# Teensy-Maxuino-Slave-A4988-stepper_2x_sh.net
KiCad netlist of a schematic drawn in EAGLE
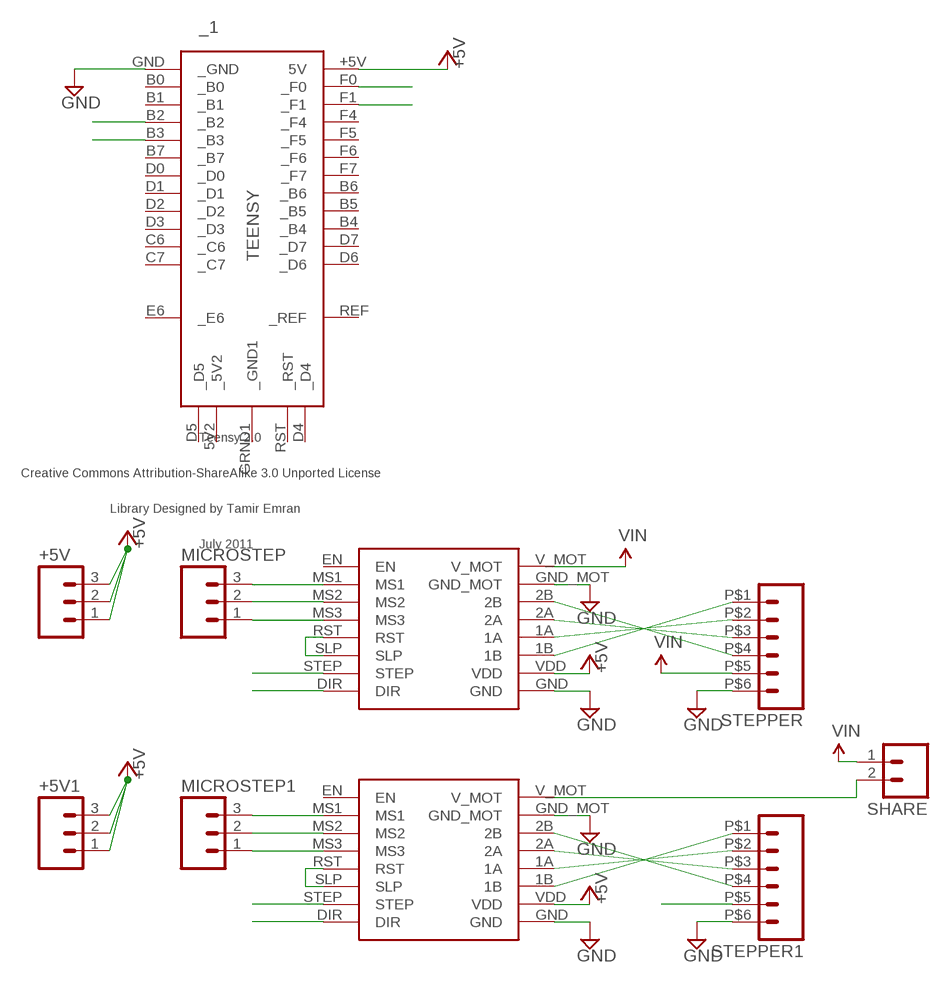
[diagram p0: schematic, sheet 1]

(export (version "E")
  (design (tool "Eeschema 10.0.6"))
  (components
    (comp (ref "+5V")
      (value "M03PTH")
      (footprint "eagle-import:1X03")
      (libsource (lib "eagle-import") (part "M03PTH"))
    )
    (comp (ref "+5V1")
      (value "M03PTH")
      (footprint "eagle-import:1X03")
      (libsource (lib "eagle-import") (part "M03PTH"))
    )
    (comp (ref "A4988_1")
      (value "POLOLU_A4988")
      (footprint "eagle-import:POLOLU_A4988")
      (libsource (lib "eagle-import") (part "POLOLU_A4988"))
    )
    (comp (ref "A4988_2")
      (value "POLOLU_A4988")
      (footprint "eagle-import:POLOLU_A4988")
      (libsource (lib "eagle-import") (part "POLOLU_A4988"))
    )
    (comp (ref "MICROSTEP")
      (value "M03PTH")
      (footprint "eagle-import:1X03")
      (libsource (lib "eagle-import") (part "M03PTH"))
    )
    (comp (ref "MICROSTEP1")
      (value "M03PTH")
      (footprint "eagle-import:1X03")
      (libsource (lib "eagle-import") (part "M03PTH"))
    )
    (comp (ref "SHARE")
      (value "M02PTH")
      (footprint "eagle-import:1X02")
      (libsource (lib "eagle-import") (part "M02PTH"))
    )
    (comp (ref "STEPPER")
      (value "M06")
      (footprint "eagle-import:SPRINGTERMINAL-2.54MM-6")
      (libsource (lib "eagle-import") (part "M06"))
    )
    (comp (ref "STEPPER1")
      (value "M06")
      (footprint "eagle-import:SPRINGTERMINAL-2.54MM-6")
      (libsource (lib "eagle-import") (part "M06"))
    )
    (comp (ref "_1")
      (value "TEENSY")
      (footprint "eagle-import:TEENSY")
      (libsource (lib "eagle-import") (part "TEENSY"))
    )
  )
  (nets
    (net (code "1") (name "+5V") (class "Default")
      (node (ref "+5V") (pin "1") (pinfunction "1_1") (pintype "passive"))
      (node (ref "+5V") (pin "2") (pinfunction "2_2") (pintype "passive"))
      (node (ref "+5V") (pin "3") (pinfunction "3_3") (pintype "passive"))
      (node (ref "+5V1") (pin "1") (pinfunction "1_1") (pintype "passive"))
      (node (ref "+5V1") (pin "2") (pinfunction "2_2") (pintype "passive"))
      (node (ref "+5V1") (pin "3") (pinfunction "3_3") (pintype "passive"))
      (node (ref "A4988_1") (pin "VDD") (pinfunction "VDD_VDD") (pintype "bidirectional"))
      (node (ref "A4988_2") (pin "VDD") (pinfunction "VDD_VDD") (pintype "bidirectional"))
      (node (ref "_1") (pin "+5V") (pinfunction "5V_+5V") (pintype "bidirectional"))
    )
    (net (code "2") (name "/DIR") (class "Default")
      (node (ref "A4988_1") (pin "DIR") (pinfunction "DIR_DIR") (pintype "bidirectional"))
      (node (ref "_1") (pin "F0") (pinfunction "_F0_F0") (pintype "bidirectional"))
    )
    (net (code "3") (name "/DIR1") (class "Default")
      (node (ref "A4988_2") (pin "DIR") (pinfunction "DIR_DIR") (pintype "bidirectional"))
      (node (ref "_1") (pin "B3") (pinfunction "_B3_B3") (pintype "bidirectional"))
    )
    (net (code "4") (name "/STEP") (class "Default")
      (node (ref "A4988_1") (pin "STEP") (pinfunction "STEP_STEP") (pintype "bidirectional"))
      (node (ref "_1") (pin "F1") (pinfunction "_F1_F1") (pintype "bidirectional"))
    )
    (net (code "5") (name "/STEP1") (class "Default")
      (node (ref "A4988_2") (pin "STEP") (pinfunction "STEP_STEP") (pintype "bidirectional"))
      (node (ref "_1") (pin "B2") (pinfunction "_B2_B2") (pintype "bidirectional"))
    )
    (net (code "6") (name "/VIN_2") (class "Default")
      (node (ref "A4988_2") (pin "V_MOT") (pinfunction "V_MOT_V_MOT") (pintype "bidirectional"))
      (node (ref "SHARE") (pin "2") (pinfunction "2_2") (pintype "passive"))
      (node (ref "STEPPER1") (pin "P$5") (pinfunction "5_P$5") (pintype "passive"))
    )
    (net (code "7") (name "GND") (class "Default")
      (node (ref "A4988_1") (pin "GND") (pinfunction "GND_GND") (pintype "bidirectional"))
      (node (ref "A4988_1") (pin "GND_MOT") (pinfunction "GND_MOT_GND_MOT") (pintype "bidirectional"))
      (node (ref "A4988_2") (pin "GND") (pinfunction "GND_GND") (pintype "bidirectional"))
      (node (ref "A4988_2") (pin "GND_MOT") (pinfunction "GND_MOT_GND_MOT") (pintype "bidirectional"))
      (node (ref "STEPPER") (pin "P$6") (pinfunction "6_P$6") (pintype "passive"))
      (node (ref "STEPPER1") (pin "P$6") (pinfunction "6_P$6") (pintype "passive"))
      (node (ref "_1") (pin "GND") (pinfunction "_GND_GND") (pintype "bidirectional"))
    )
    (net (code "8") (name "Net-(A4988_1-PadMS1)") (class "Default")
      (node (ref "A4988_1") (pin "MS1") (pinfunction "MS1_MS1") (pintype "bidirectional"))
      (node (ref "MICROSTEP") (pin "3") (pinfunction "3_3") (pintype "passive"))
    )
    (net (code "9") (name "Net-(A4988_1-PadMS2)") (class "Default")
      (node (ref "A4988_1") (pin "MS2") (pinfunction "MS2_MS2") (pintype "bidirectional"))
      (node (ref "MICROSTEP") (pin "2") (pinfunction "2_2") (pintype "passive"))
    )
    (net (code "10") (name "Net-(A4988_1-PadMS3)") (class "Default")
      (node (ref "A4988_1") (pin "MS3") (pinfunction "MS3_MS3") (pintype "bidirectional"))
      (node (ref "MICROSTEP") (pin "1") (pinfunction "1_1") (pintype "passive"))
    )
    (net (code "11") (name "Net-(A4988_1-PadRST)") (class "Default")
      (node (ref "A4988_1") (pin "RST") (pinfunction "RST_RST") (pintype "bidirectional"))
      (node (ref "A4988_1") (pin "SLP") (pinfunction "SLP_SLP") (pintype "bidirectional"))
    )
    (net (code "12") (name "Net-(A4988_2-PadMS1)") (class "Default")
      (node (ref "A4988_2") (pin "MS1") (pinfunction "MS1_MS1") (pintype "bidirectional"))
      (node (ref "MICROSTEP1") (pin "3") (pinfunction "3_3") (pintype "passive"))
    )
    (net (code "13") (name "Net-(A4988_2-PadMS2)") (class "Default")
      (node (ref "A4988_2") (pin "MS2") (pinfunction "MS2_MS2") (pintype "bidirectional"))
      (node (ref "MICROSTEP1") (pin "2") (pinfunction "2_2") (pintype "passive"))
    )
    (net (code "14") (name "Net-(A4988_2-PadMS3)") (class "Default")
      (node (ref "A4988_2") (pin "MS3") (pinfunction "MS3_MS3") (pintype "bidirectional"))
      (node (ref "MICROSTEP1") (pin "1") (pinfunction "1_1") (pintype "passive"))
    )
    (net (code "15") (name "Net-(A4988_2-PadRST)") (class "Default")
      (node (ref "A4988_2") (pin "RST") (pinfunction "RST_RST") (pintype "bidirectional"))
      (node (ref "A4988_2") (pin "SLP") (pinfunction "SLP_SLP") (pintype "bidirectional"))
    )
    (net (code "16") (name "Net-(STEPPER-1)") (class "Default")
      (node (ref "A4988_1") (pin "1B") (pinfunction "1B_1B") (pintype "bidirectional"))
      (node (ref "STEPPER") (pin "P$1") (pinfunction "1_P$1") (pintype "passive"))
    )
    (net (code "17") (name "Net-(STEPPER-2)") (class "Default")
      (node (ref "A4988_1") (pin "1A") (pinfunction "1A_1A") (pintype "bidirectional"))
      (node (ref "STEPPER") (pin "P$2") (pinfunction "2_P$2") (pintype "passive"))
    )
    (net (code "18") (name "Net-(STEPPER-3)") (class "Default")
      (node (ref "A4988_1") (pin "2A") (pinfunction "2A_2A") (pintype "bidirectional"))
      (node (ref "STEPPER") (pin "P$3") (pinfunction "3_P$3") (pintype "passive"))
    )
    (net (code "19") (name "Net-(STEPPER-4)") (class "Default")
      (node (ref "A4988_1") (pin "2B") (pinfunction "2B_2B") (pintype "bidirectional"))
      (node (ref "STEPPER") (pin "P$4") (pinfunction "4_P$4") (pintype "passive"))
    )
    (net (code "20") (name "Net-(STEPPER1-1)") (class "Default")
      (node (ref "A4988_2") (pin "1B") (pinfunction "1B_1B") (pintype "bidirectional"))
      (node (ref "STEPPER1") (pin "P$1") (pinfunction "1_P$1") (pintype "passive"))
    )
    (net (code "21") (name "Net-(STEPPER1-2)") (class "Default")
      (node (ref "A4988_2") (pin "1A") (pinfunction "1A_1A") (pintype "bidirectional"))
      (node (ref "STEPPER1") (pin "P$2") (pinfunction "2_P$2") (pintype "passive"))
    )
    (net (code "22") (name "Net-(STEPPER1-3)") (class "Default")
      (node (ref "A4988_2") (pin "2A") (pinfunction "2A_2A") (pintype "bidirectional"))
      (node (ref "STEPPER1") (pin "P$3") (pinfunction "3_P$3") (pintype "passive"))
    )
    (net (code "23") (name "Net-(STEPPER1-4)") (class "Default")
      (node (ref "A4988_2") (pin "2B") (pinfunction "2B_2B") (pintype "bidirectional"))
      (node (ref "STEPPER1") (pin "P$4") (pinfunction "4_P$4") (pintype "passive"))
    )
    (net (code "24") (name "VIN") (class "Default")
      (node (ref "A4988_1") (pin "V_MOT") (pinfunction "V_MOT_V_MOT") (pintype "bidirectional"))
      (node (ref "SHARE") (pin "1") (pinfunction "1_1") (pintype "passive"))
      (node (ref "STEPPER") (pin "P$5") (pinfunction "5_P$5") (pintype "passive"))
    )
    (net (code "25") (name "unconnected-(A4988_1-PadEN)") (class "Default")
      (node (ref "A4988_1") (pin "EN") (pinfunction "EN_EN") (pintype "bidirectional"))
    )
    (net (code "26") (name "unconnected-(A4988_2-PadEN)") (class "Default")
      (node (ref "A4988_2") (pin "EN") (pinfunction "EN_EN") (pintype "bidirectional"))
    )
    (net (code "27") (name "unconnected-(_1-_5V2-Pad5V2)") (class "Default")
      (node (ref "_1") (pin "5V2") (pinfunction "_5V2_5V2") (pintype "bidirectional"))
    )
    (net (code "28") (name "unconnected-(_1-_B0-PadB0)") (class "Default")
      (node (ref "_1") (pin "B0") (pinfunction "_B0_B0") (pintype "bidirectional"))
    )
    (net (code "29") (name "unconnected-(_1-_B1-PadB1)") (class "Default")
      (node (ref "_1") (pin "B1") (pinfunction "_B1_B1") (pintype "bidirectional"))
    )
    (net (code "30") (name "unconnected-(_1-_B4-PadB4)") (class "Default")
      (node (ref "_1") (pin "B4") (pinfunction "_B4_B4") (pintype "bidirectional"))
    )
    (net (code "31") (name "unconnected-(_1-_B5-PadB5)") (class "Default")
      (node (ref "_1") (pin "B5") (pinfunction "_B5_B5") (pintype "bidirectional"))
    )
    (net (code "32") (name "unconnected-(_1-_B6-PadB6)") (class "Default")
      (node (ref "_1") (pin "B6") (pinfunction "_B6_B6") (pintype "bidirectional"))
    )
    (net (code "33") (name "unconnected-(_1-_B7-PadB7)") (class "Default")
      (node (ref "_1") (pin "B7") (pinfunction "_B7_B7") (pintype "bidirectional"))
    )
    (net (code "34") (name "unconnected-(_1-_C6-PadC6)") (class "Default")
      (node (ref "_1") (pin "C6") (pinfunction "_C6_C6") (pintype "bidirectional"))
    )
    (net (code "35") (name "unconnected-(_1-_C7-PadC7)") (class "Default")
      (node (ref "_1") (pin "C7") (pinfunction "_C7_C7") (pintype "bidirectional"))
    )
    (net (code "36") (name "unconnected-(_1-_D0-PadD0)") (class "Default")
      (node (ref "_1") (pin "D0") (pinfunction "_D0_D0") (pintype "bidirectional"))
    )
    (net (code "37") (name "unconnected-(_1-_D1-PadD1)") (class "Default")
      (node (ref "_1") (pin "D1") (pinfunction "_D1_D1") (pintype "bidirectional"))
    )
    (net (code "38") (name "unconnected-(_1-_D2-PadD2)") (class "Default")
      (node (ref "_1") (pin "D2") (pinfunction "_D2_D2") (pintype "bidirectional"))
    )
    (net (code "39") (name "unconnected-(_1-_D3-PadD3)") (class "Default")
      (node (ref "_1") (pin "D3") (pinfunction "_D3_D3") (pintype "bidirectional"))
    )
    (net (code "40") (name "unconnected-(_1-_D4-PadD4)") (class "Default")
      (node (ref "_1") (pin "D4") (pinfunction "_D4_D4") (pintype "bidirectional"))
    )
    (net (code "41") (name "unconnected-(_1-_D5-PadD5)") (class "Default")
      (node (ref "_1") (pin "D5") (pinfunction "_D5_D5") (pintype "bidirectional"))
    )
    (net (code "42") (name "unconnected-(_1-_D6-PadD6)") (class "Default")
      (node (ref "_1") (pin "D6") (pinfunction "_D6_D6") (pintype "bidirectional"))
    )
    (net (code "43") (name "unconnected-(_1-_D7-PadD7)") (class "Default")
      (node (ref "_1") (pin "D7") (pinfunction "_D7_D7") (pintype "bidirectional"))
    )
    (net (code "44") (name "unconnected-(_1-_E6-PadE6)") (class "Default")
      (node (ref "_1") (pin "E6") (pinfunction "_E6_E6") (pintype "bidirectional"))
    )
    (net (code "45") (name "unconnected-(_1-_F4-PadF4)") (class "Default")
      (node (ref "_1") (pin "F4") (pinfunction "_F4_F4") (pintype "bidirectional"))
    )
    (net (code "46") (name "unconnected-(_1-_F5-PadF5)") (class "Default")
      (node (ref "_1") (pin "F5") (pinfunction "_F5_F5") (pintype "bidirectional"))
    )
    (net (code "47") (name "unconnected-(_1-_F6-PadF6)") (class "Default")
      (node (ref "_1") (pin "F6") (pinfunction "_F6_F6") (pintype "bidirectional"))
    )
    (net (code "48") (name "unconnected-(_1-_F7-PadF7)") (class "Default")
      (node (ref "_1") (pin "F7") (pinfunction "_F7_F7") (pintype "bidirectional"))
    )
    (net (code "49") (name "unconnected-(_1-_GND1-PadGRND1)") (class "Default")
      (node (ref "_1") (pin "GRND1") (pinfunction "_GND1_GRND1") (pintype "bidirectional"))
    )
    (net (code "50") (name "unconnected-(_1-_REF-PadREF)") (class "Default")
      (node (ref "_1") (pin "REF") (pinfunction "_REF_REF") (pintype "bidirectional"))
    )
    (net (code "51") (name "unconnected-(_1-_RST-PadRST)") (class "Default")
      (node (ref "_1") (pin "RST") (pinfunction "_RST_RST") (pintype "bidirectional"))
    )
  )
)
